# ELRS.net
KiCad netlist of a schematic drawn in Altium Designer
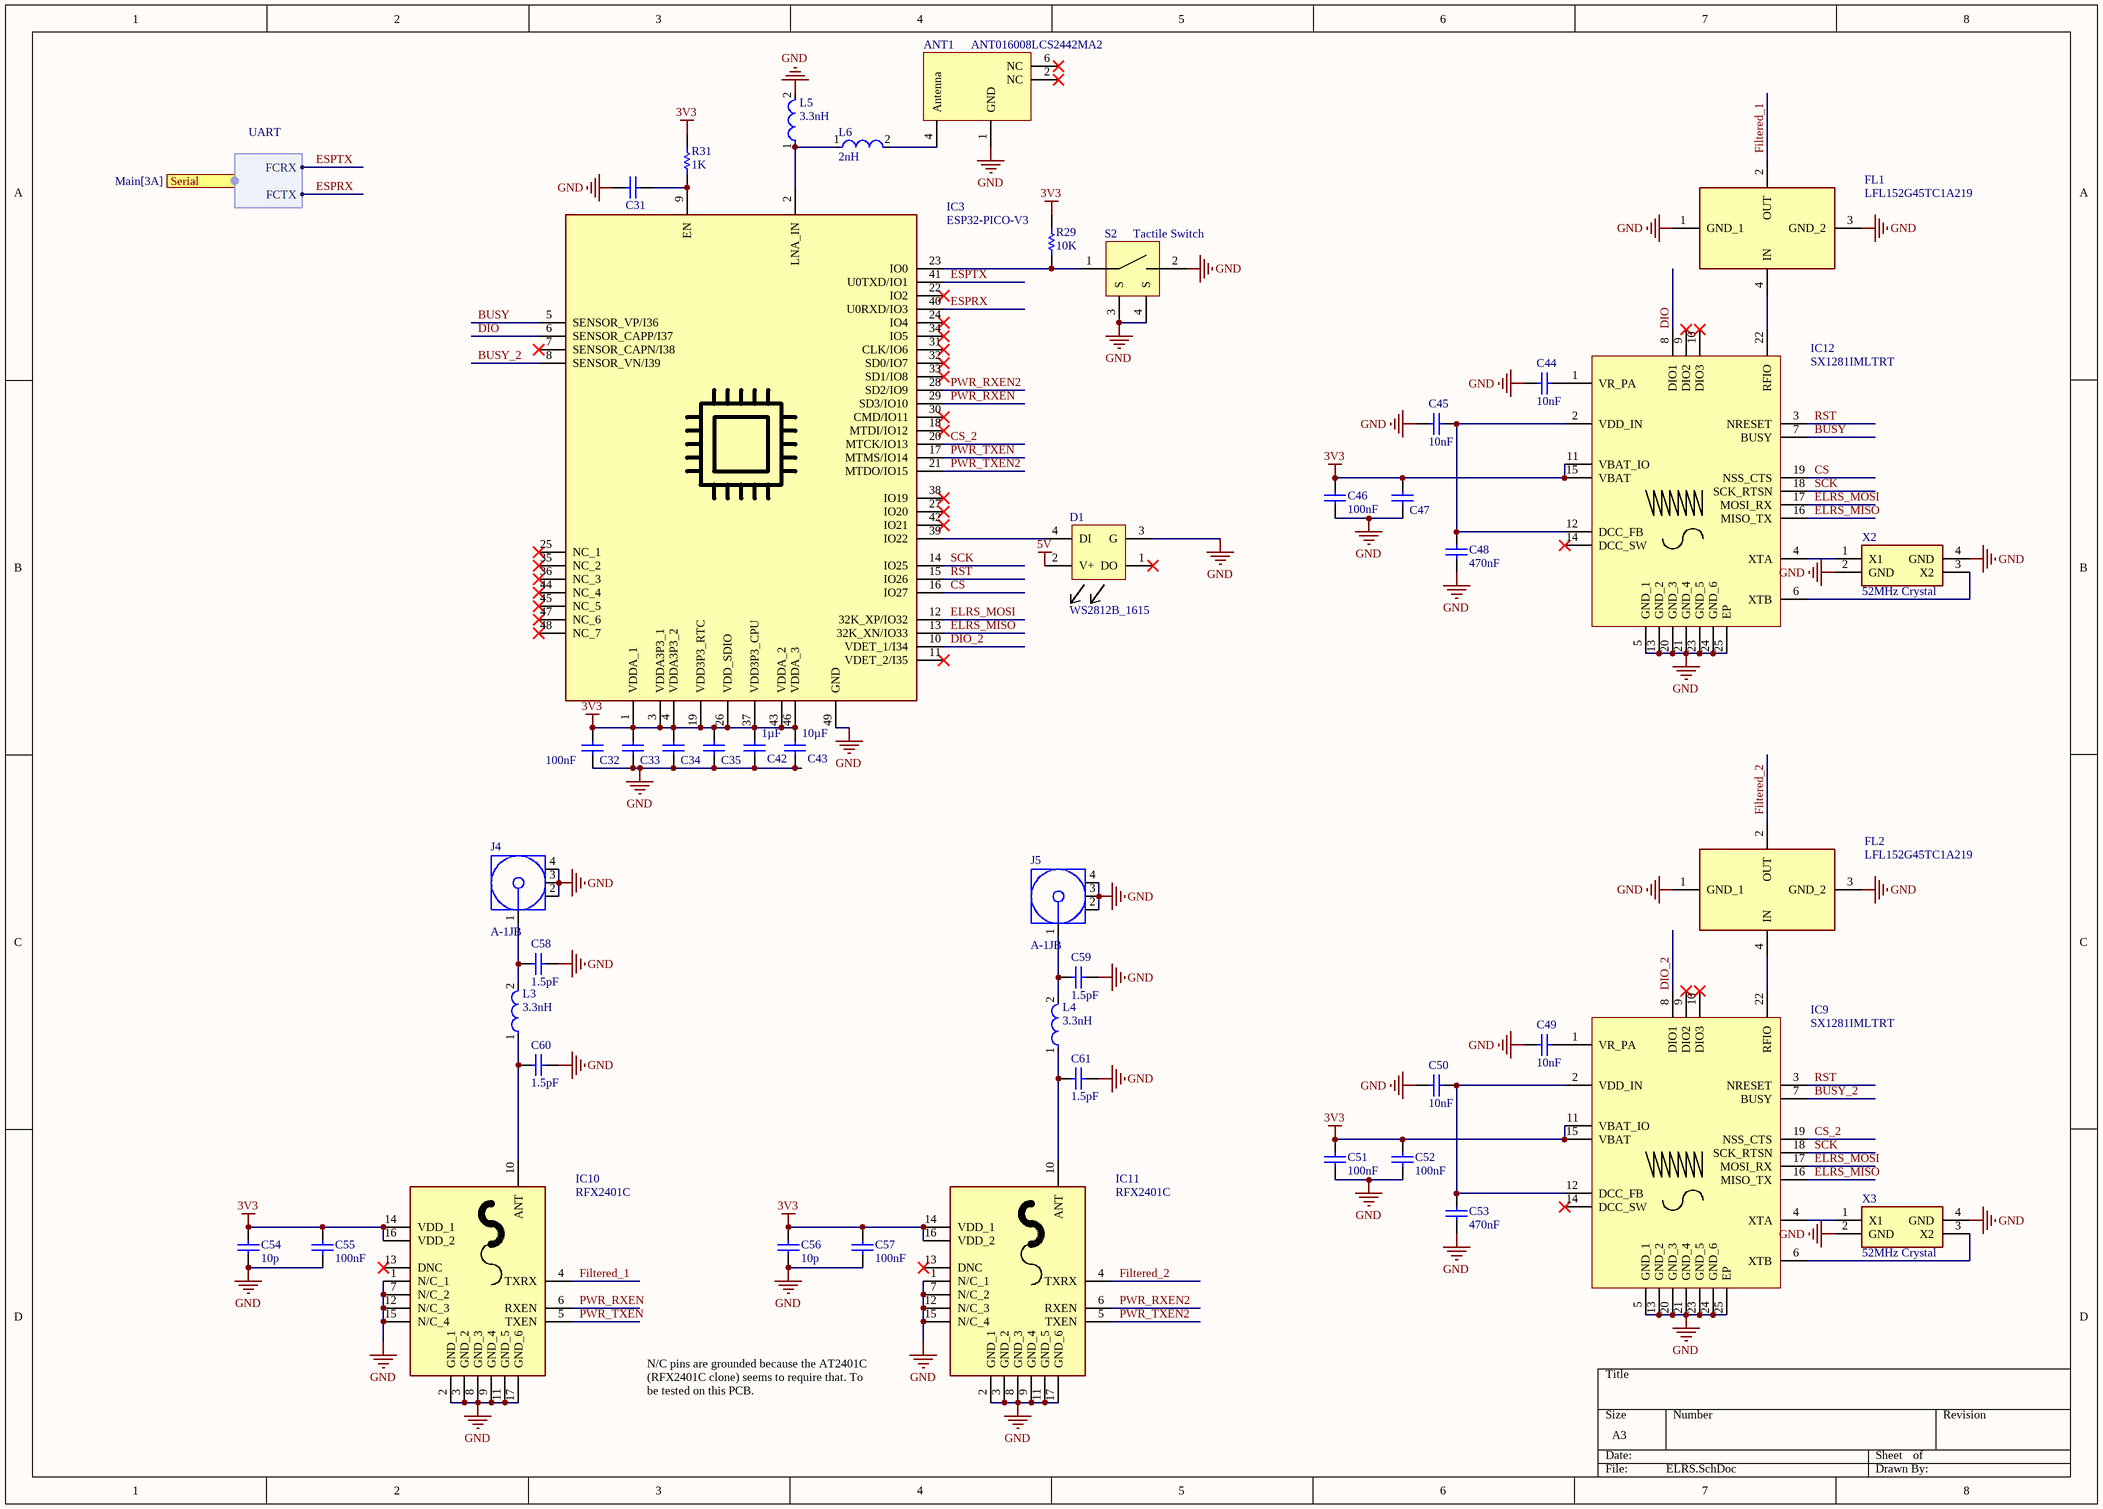
[diagram p0: ELRS.SchDoc]

(export (version "E")
  (design (tool "Eeschema 10.0.6"))
  (components
    (comp (ref "ANT1")
      (value "ANT016008LCS2442MA2")
      (footprint "Custom Components:ANT016008LCS2442MA2")
      (description "Antenna")
      (fields (field (name "MOUSER PART NUMBER") "810-ANT168LCS2442MA2"))
      (libsource (lib "Custom Components") (part "ANT016008LCS2442MA2"))
    )
    (comp (ref "C31")
      (value "100nF")
      (footprint "WCAP-CSGP_0603_L1.6W0.8H0.8_Reflow")
      (description "WCAP-CSGP Multilayer Ceramic Chip Capacitor, General Purpose, size 0603, X7R, 100nF, 50VDC")
      (fields
        (field (name "MANUFACTURER PART NUMBER") "885012206095")
        (field (name "MANUFACTURER") "Wurth Elektronik")
      )
      (libsource (lib "Altium_WCAP-CSGP (rev22f)") (part "885012206095"))
    )
    (comp (ref "C32")
      (value "100nF")
      (footprint "WCAP-CSGP_0603_L1.6W0.8H0.8_Reflow")
      (description "WCAP-CSGP Multilayer Ceramic Chip Capacitor, General Purpose, size 0603, X7R, 100nF, 50VDC")
      (fields
        (field (name "MANUFACTURER PART NUMBER") "885012206095")
        (field (name "MANUFACTURER") "Wurth Elektronik")
      )
      (libsource (lib "Altium_WCAP-CSGP (rev22f)") (part "885012206095"))
    )
    (comp (ref "C33")
      (value "100nF")
      (footprint "WCAP-CSGP_0603_L1.6W0.8H0.8_Reflow")
      (description "WCAP-CSGP Multilayer Ceramic Chip Capacitor, General Purpose, size 0603, X7R, 100nF, 50VDC")
      (fields
        (field (name "MANUFACTURER PART NUMBER") "885012206095")
        (field (name "MANUFACTURER") "Wurth Elektronik")
      )
      (libsource (lib "Altium_WCAP-CSGP (rev22f)") (part "885012206095"))
    )
    (comp (ref "C34")
      (value "100nF")
      (footprint "WCAP-CSGP_0603_L1.6W0.8H0.8_Reflow")
      (description "WCAP-CSGP Multilayer Ceramic Chip Capacitor, General Purpose, size 0603, X7R, 100nF, 50VDC")
      (fields
        (field (name "MANUFACTURER PART NUMBER") "885012206095")
        (field (name "MANUFACTURER") "Wurth Elektronik")
      )
      (libsource (lib "Altium_WCAP-CSGP (rev22f)") (part "885012206095"))
    )
    (comp (ref "C35")
      (value "100nF")
      (footprint "WCAP-CSGP_0603_L1.6W0.8H0.8_Reflow")
      (description "WCAP-CSGP Multilayer Ceramic Chip Capacitor, General Purpose, size 0603, X7R, 100nF, 50VDC")
      (fields
        (field (name "MANUFACTURER PART NUMBER") "885012206095")
        (field (name "MANUFACTURER") "Wurth Elektronik")
      )
      (libsource (lib "Altium_WCAP-CSGP (rev22f)") (part "885012206095"))
    )
    (comp (ref "C42")
      (value "1µF")
      (footprint "WCAP-CSGP_0603_L1.6W0.8H0.8_Reflow")
      (description "WCAP-CSGP Multilayer Ceramic Chip Capacitor, General Purpose, size 0603, X7R, 1µF, 25VDC")
      (fields
        (field (name "MANUFACTURER PART NUMBER") "885012206076")
        (field (name "MANUFACTURER") "Wurth Elektronik")
      )
      (libsource (lib "Altium_WCAP-CSGP (rev22f)") (part "885012206076"))
    )
    (comp (ref "C43")
      (value "10µF")
      (footprint "WCAP-CSGP_0603_L1.6W0.8H0.8_Reflow")
      (description "WCAP-CSGP Multilayer Ceramic Chip Capacitor, General Purpose, size 0603, X5R, 10µF, 25VDC")
      (fields
        (field (name "MANUFACTURER PART NUMBER") "885012106031")
        (field (name "MANUFACTURER") "Wurth Elektronik")
      )
      (libsource (lib "Altium_WCAP-CSGP (rev22f)") (part "885012106031"))
    )
    (comp (ref "C44")
      (value "10nF")
      (footprint "0402 cap")
      (libsource (lib "Custom Components") (part "Capacitor 0402 100nF"))
    )
    (comp (ref "C45")
      (value "10nF")
      (footprint "0402 cap")
      (libsource (lib "Custom Components") (part "Capacitor 0402 100nF"))
    )
    (comp (ref "C46")
      (value "100nF")
      (footprint "0402 cap")
      (libsource (lib "Custom Components") (part "Capacitor 0402 100nF"))
    )
    (comp (ref "C47")
      (value "100nF")
      (footprint "WCAP-CSGP_0603_L1.6W0.8H0.8_Reflow")
      (description "WCAP-CSGP Multilayer Ceramic Chip Capacitor, General Purpose, size 0603, X7R, 100nF, 50VDC")
      (fields
        (field (name "MANUFACTURER PART NUMBER") "885012206095")
        (field (name "MANUFACTURER") "Wurth Elektronik")
      )
      (libsource (lib "Altium_WCAP-CSGP (rev22f)") (part "885012206095"))
    )
    (comp (ref "C48")
      (value "470nF")
      (footprint "0402 cap")
      (libsource (lib "Custom Components") (part "Capacitor 0402 100nF"))
    )
    (comp (ref "C49")
      (value "10nF")
      (footprint "0402 cap")
      (libsource (lib "Custom Components") (part "Capacitor 0402 100nF"))
    )
    (comp (ref "C50")
      (value "10nF")
      (footprint "0402 cap")
      (libsource (lib "Custom Components") (part "Capacitor 0402 100nF"))
    )
    (comp (ref "C51")
      (value "100nF")
      (footprint "0402 cap")
      (libsource (lib "Custom Components") (part "Capacitor 0402 100nF"))
    )
    (comp (ref "C52")
      (value "100nF")
      (footprint "0402 cap")
      (libsource (lib "Custom Components") (part "Capacitor 0402 100nF"))
    )
    (comp (ref "C53")
      (value "470nF")
      (footprint "0402 cap")
      (libsource (lib "Custom Components") (part "Capacitor 0402 100nF"))
    )
    (comp (ref "C54")
      (value "10p")
      (footprint "0402 cap")
      (libsource (lib "Custom Components") (part "Capacitor 0402 100nF"))
    )
    (comp (ref "C55")
      (value "100nF")
      (footprint "0402 cap")
      (libsource (lib "Custom Components") (part "Capacitor 0402 100nF"))
    )
    (comp (ref "C56")
      (value "10p")
      (footprint "0402 cap")
      (libsource (lib "Custom Components") (part "Capacitor 0402 100nF"))
    )
    (comp (ref "C57")
      (value "100nF")
      (footprint "0402 cap")
      (libsource (lib "Custom Components") (part "Capacitor 0402 100nF"))
    )
    (comp (ref "C58")
      (value "1.5pF")
      (footprint "0402 cap")
      (description "CL05C1R5BB5NNNC")
      (libsource (lib "Custom Components") (part "Capacitor 0402 100nF"))
    )
    (comp (ref "C59")
      (value "1.5pF")
      (footprint "0402 cap")
      (description "CL05C1R5BB5NNNC")
      (libsource (lib "Custom Components") (part "Capacitor 0402 100nF"))
    )
    (comp (ref "C60")
      (value "1.5pF")
      (footprint "0402 cap")
      (description "CL05C1R5BB5NNNC")
      (libsource (lib "Custom Components") (part "Capacitor 0402 100nF"))
    )
    (comp (ref "C61")
      (value "1.5pF")
      (footprint "0402 cap")
      (description "CL05C1R5BB5NNNC")
      (libsource (lib "Custom Components") (part "Capacitor 0402 100nF"))
    )
    (comp (ref "D1")
      (value "WS2812B_1615")
      (footprint "WS2812B_1615")
      (description "XINGLIGHT XL-1615RGBC-WS2812B")
      (libsource (lib "Custom Components") (part "WS2812B_1615"))
    )
    (comp (ref "FL1")
      (value "LFL152G45TC1A219")
      (footprint "Custom Components:LFL152G45TC1A219")
      (description "Filter")
      (fields (field (name "MOUSER PART NUMBER") "81-LFL152G45TC1A219"))
      (libsource (lib "*") (part "LFL152G45TC1A219"))
    )
    (comp (ref "FL2")
      (value "LFL152G45TC1A219")
      (footprint "Custom Components:LFL152G45TC1A219")
      (description "Filter")
      (fields (field (name "MOUSER PART NUMBER") "81-LFL152G45TC1A219"))
      (libsource (lib "*") (part "LFL152G45TC1A219"))
    )
    (comp (ref "IC3")
      (value "ESP32-PICO-V3")
      (footprint "Custom Components:ESP32PICOV3")
      (description "Integrated Circuit")
      (fields (field (name "MOUSER PART NUMBER") "356-ESP32-PICO-V3"))
      (libsource (lib "Custom Components") (part "ESP32-PICO-V3"))
    )
    (comp (ref "IC9")
      (value "SX1281IMLTRT")
      (footprint "Custom Components:QFN50P400X400X100-25N-D")
      (description "Integrated Circuit")
      (fields (field (name "MOUSER PART NUMBER") "947-SX1281IMLTRT"))
      (libsource (lib "Custom Components") (part "SX1281IMLTRT"))
    )
    (comp (ref "IC10")
      (value "RFX2401C")
      (footprint "Custom Components:QFN50P300X300X60-17N-D")
      (description "Integrated Circuit")
      (fields (field (name "MOUSER PART NUMBER") "477-RFX2401C"))
      (libsource (lib "Custom Components") (part "RFX2401C"))
    )
    (comp (ref "IC11")
      (value "RFX2401C")
      (footprint "Custom Components:QFN50P300X300X60-17N-D")
      (description "Integrated Circuit")
      (fields (field (name "MOUSER PART NUMBER") "477-RFX2401C"))
      (libsource (lib "Custom Components") (part "RFX2401C"))
    )
    (comp (ref "IC12")
      (value "SX1281IMLTRT")
      (footprint "Custom Components:QFN50P400X400X100-25N-D")
      (description "Integrated Circuit")
      (fields (field (name "MOUSER PART NUMBER") "947-SX1281IMLTRT"))
      (libsource (lib "Custom Components") (part "SX1281IMLTRT"))
    )
    (comp (ref "J4")
      (value "A-1JB")
      (footprint "AMPH-A-1JB_V")
      (description "AMC PCB Jack, 0 to 60 GHz, 60 V, -40 to 90 degC, 4-Pin SMD, RoHS, Tape and Reel")
      (fields (field (name "TOLERANCE") "10%"))
      (libsource (lib "Altium Content Vault") (part "CN-S-3F-RF4"))
    )
    (comp (ref "J5")
      (value "A-1JB")
      (footprint "AMPH-A-1JB_V")
      (description "AMC PCB Jack, 0 to 60 GHz, 60 V, -40 to 90 degC, 4-Pin SMD, RoHS, Tape and Reel")
      (fields (field (name "TOLERANCE") "10%"))
      (libsource (lib "Altium Content Vault") (part "CN-S-3F-RF4"))
    )
    (comp (ref "L3")
      (value "3.3nH")
      (footprint "FP-LQW15AN_00-W0_6-0_1-MFG")
      (description "MLG1005S3N3BT000")
      (libsource (lib "Altium Content Vault") (part "725321dda6339637d4d059423bc1c3c"))
    )
    (comp (ref "L4")
      (value "3.3nH")
      (footprint "FP-LQW15AN_00-W0_6-0_1-MFG")
      (description "MLG1005S3N3BT000")
      (libsource (lib "Altium Content Vault") (part "725321dda6339637d4d059423bc1c3c"))
    )
    (comp (ref "L5")
      (value "3.3nH")
      (footprint "FP-LQW15AN_00-W0_6-0_1-MFG")
      (description "MLG1005S3N3BT000")
      (libsource (lib "Altium Content Vault") (part "725321dda6339637d4d059423bc1c3c"))
    )
    (comp (ref "L6")
      (value "2nH")
      (footprint "FP-LQW15AN_00-W0_6-0_1-MFG")
      (description "MLG1005S3N3BT000")
      (libsource (lib "Altium Content Vault") (part "725321dda6339637d4d059423bc1c3c"))
    )
    (comp (ref "R29")
      (value "10K")
      (footprint "Custom Components:0402 resistor")
      (libsource (lib "Custom Components") (part "Resistor 0402 1K"))
    )
    (comp (ref "R31")
      (value "1K")
      (footprint "Custom Components:0402 resistor")
      (libsource (lib "Custom Components") (part "Resistor 0402 1K"))
    )
    (comp (ref "S2")
      (value "Tactile Switch")
      (footprint "Tactile Switch")
      (libsource (lib "Custom Components") (part "Tactile Switch"))
    )
    (comp (ref "X2")
      (value "52MHz Crystal")
      (footprint "2016 Crystal")
      (description "HCI XC21M4-52.000-F10NNHPL")
      (libsource (lib "Custom Components") (part "HCI XC21M4-52.000"))
    )
    (comp (ref "X3")
      (value "52MHz Crystal")
      (footprint "2016 Crystal")
      (description "HCI XC21M4-52.000-F10NNHPL")
      (libsource (lib "Custom Components") (part "HCI XC21M4-52.000"))
    )
  )
  (nets
    (net (code "2") (name "/BUSY") (class "Default")
      (node (ref "IC12") (pin "7") (pinfunction "BUSY_7") (pintype "passive"))
      (node (ref "IC3") (pin "5") (pinfunction "SENSOR_VP/I36_5") (pintype "passive"))
    )
    (net (code "3") (name "/BUSY_2") (class "Default")
      (node (ref "IC3") (pin "8") (pinfunction "SENSOR_VN/I39_8") (pintype "passive"))
      (node (ref "IC9") (pin "7") (pinfunction "BUSY_7") (pintype "passive"))
    )
    (net (code "4") (name "/CS") (class "Default")
      (node (ref "IC12") (pin "19") (pinfunction "NSS_CTS_19") (pintype "passive"))
      (node (ref "IC3") (pin "16") (pinfunction "IO27_16") (pintype "passive"))
    )
    (net (code "5") (name "/CS_2") (class "Default")
      (node (ref "IC3") (pin "20") (pinfunction "MTCK/IO13_20") (pintype "passive"))
      (node (ref "IC9") (pin "19") (pinfunction "NSS_CTS_19") (pintype "passive"))
    )
    (net (code "6") (name "/DIO") (class "Default")
      (node (ref "IC12") (pin "8") (pinfunction "DIO1_8") (pintype "passive"))
      (node (ref "IC3") (pin "6") (pinfunction "SENSOR_CAPP/I37_6") (pintype "passive"))
    )
    (net (code "7") (name "/DIO_2") (class "Default")
      (node (ref "IC3") (pin "10") (pinfunction "VDET_1/I34_10") (pintype "passive"))
      (node (ref "IC9") (pin "8") (pinfunction "DIO1_8") (pintype "passive"))
    )
    (net (code "8") (name "/ELRS_MISO") (class "Default")
      (node (ref "IC12") (pin "16") (pinfunction "MISO_TX_16") (pintype "passive"))
      (node (ref "IC3") (pin "13") (pinfunction "32K_XN/IO33_13") (pintype "passive"))
      (node (ref "IC9") (pin "16") (pinfunction "MISO_TX_16") (pintype "passive"))
    )
    (net (code "9") (name "/ELRS_MOSI") (class "Default")
      (node (ref "IC12") (pin "17") (pinfunction "MOSI_RX_17") (pintype "passive"))
      (node (ref "IC3") (pin "12") (pinfunction "32K_XP/IO32_12") (pintype "passive"))
      (node (ref "IC9") (pin "17") (pinfunction "MOSI_RX_17") (pintype "passive"))
    )
    (net (code "10") (name "/ESPRX") (class "Default")
      (node (ref "IC3") (pin "40") (pinfunction "U0RXD/IO3_40") (pintype "passive"))
    )
    (net (code "11") (name "/ESPTX") (class "Default")
      (node (ref "IC3") (pin "41") (pinfunction "U0TXD/IO1_41") (pintype "passive"))
    )
    (net (code "12") (name "/Filtered_1") (class "Default")
      (node (ref "FL1") (pin "2") (pinfunction "OUT_2") (pintype "passive"))
      (node (ref "IC10") (pin "4") (pinfunction "TXRX_4") (pintype "passive"))
    )
    (net (code "13") (name "/Filtered_2") (class "Default")
      (node (ref "FL2") (pin "2") (pinfunction "OUT_2") (pintype "passive"))
      (node (ref "IC11") (pin "4") (pinfunction "TXRX_4") (pintype "passive"))
    )
    (net (code "14") (name "/PWR_RXEN") (class "Default")
      (node (ref "IC10") (pin "6") (pinfunction "RXEN_6") (pintype "passive"))
      (node (ref "IC3") (pin "29") (pinfunction "SD3/IO10_29") (pintype "passive"))
    )
    (net (code "15") (name "/PWR_RXEN2") (class "Default")
      (node (ref "IC11") (pin "6") (pinfunction "RXEN_6") (pintype "passive"))
      (node (ref "IC3") (pin "28") (pinfunction "SD2/IO9_28") (pintype "passive"))
    )
    (net (code "16") (name "/PWR_TXEN") (class "Default")
      (node (ref "IC10") (pin "5") (pinfunction "TXEN_5") (pintype "passive"))
      (node (ref "IC3") (pin "17") (pinfunction "MTMS/IO14_17") (pintype "passive"))
    )
    (net (code "17") (name "/PWR_TXEN2") (class "Default")
      (node (ref "IC11") (pin "5") (pinfunction "TXEN_5") (pintype "passive"))
      (node (ref "IC3") (pin "21") (pinfunction "MTDO/IO15_21") (pintype "passive"))
    )
    (net (code "18") (name "/RST") (class "Default")
      (node (ref "IC12") (pin "3") (pinfunction "NRESET_3") (pintype "passive"))
      (node (ref "IC3") (pin "15") (pinfunction "IO26_15") (pintype "passive"))
      (node (ref "IC9") (pin "3") (pinfunction "NRESET_3") (pintype "passive"))
    )
    (net (code "19") (name "/SCK") (class "Default")
      (node (ref "IC12") (pin "18") (pinfunction "SCK_RTSN_18") (pintype "passive"))
      (node (ref "IC3") (pin "14") (pinfunction "IO25_14") (pintype "passive"))
      (node (ref "IC9") (pin "18") (pinfunction "SCK_RTSN_18") (pintype "passive"))
    )
    (net (code "21") (name "3V3") (class "Default")
      (node (ref "C32") (pin "2") (pinfunction "2_2") (pintype "passive"))
      (node (ref "C33") (pin "2") (pinfunction "2_2") (pintype "passive"))
      (node (ref "C34") (pin "2") (pinfunction "2_2") (pintype "passive"))
      (node (ref "C35") (pin "2") (pinfunction "2_2") (pintype "passive"))
      (node (ref "C42") (pin "2") (pinfunction "2_2") (pintype "passive"))
      (node (ref "C43") (pin "2") (pinfunction "2_2") (pintype "passive"))
      (node (ref "C46") (pin "2") (pinfunction "2_2") (pintype "passive"))
      (node (ref "C47") (pin "2") (pinfunction "2_2") (pintype "passive"))
      (node (ref "C51") (pin "2") (pinfunction "2_2") (pintype "passive"))
      (node (ref "C52") (pin "2") (pinfunction "2_2") (pintype "passive"))
      (node (ref "C54") (pin "2") (pinfunction "2_2") (pintype "passive"))
      (node (ref "C55") (pin "2") (pinfunction "2_2") (pintype "passive"))
      (node (ref "C56") (pin "2") (pinfunction "2_2") (pintype "passive"))
      (node (ref "C57") (pin "2") (pinfunction "2_2") (pintype "passive"))
      (node (ref "IC10") (pin "14") (pinfunction "VDD_1_14") (pintype "passive"))
      (node (ref "IC10") (pin "16") (pinfunction "VDD_2_16") (pintype "passive"))
      (node (ref "IC11") (pin "14") (pinfunction "VDD_1_14") (pintype "passive"))
      (node (ref "IC11") (pin "16") (pinfunction "VDD_2_16") (pintype "passive"))
      (node (ref "IC12") (pin "11") (pinfunction "VBAT_IO_11") (pintype "passive"))
      (node (ref "IC12") (pin "15") (pinfunction "VBAT_15") (pintype "passive"))
      (node (ref "IC3") (pin "1") (pinfunction "VDDA_1_1") (pintype "passive"))
      (node (ref "IC3") (pin "19") (pinfunction "VDD3P3_RTC_19") (pintype "passive"))
      (node (ref "IC3") (pin "26") (pinfunction "VDD_SDIO_26") (pintype "passive"))
      (node (ref "IC3") (pin "3") (pinfunction "VDDA3P3_1_3") (pintype "passive"))
      (node (ref "IC3") (pin "37") (pinfunction "VDD3P3_CPU_37") (pintype "passive"))
      (node (ref "IC3") (pin "4") (pinfunction "VDDA3P3_2_4") (pintype "passive"))
      (node (ref "IC3") (pin "43") (pinfunction "VDDA_2_43") (pintype "passive"))
      (node (ref "IC3") (pin "46") (pinfunction "VDDA_3_46") (pintype "passive"))
      (node (ref "IC9") (pin "11") (pinfunction "VBAT_IO_11") (pintype "passive"))
      (node (ref "IC9") (pin "15") (pinfunction "VBAT_15") (pintype "passive"))
      (node (ref "R29") (pin "2") (pinfunction "2_2") (pintype "passive"))
      (node (ref "R31") (pin "2") (pinfunction "2_2") (pintype "passive"))
    )
    (net (code "22") (name "5V") (class "Default")
      (node (ref "D1") (pin "2") (pinfunction "V+_2") (pintype "passive"))
    )
    (net (code "23") (name "GND") (class "Default")
      (node (ref "ANT1") (pin "1") (pinfunction "GND_1") (pintype "passive"))
      (node (ref "C31") (pin "2") (pinfunction "2_2") (pintype "passive"))
      (node (ref "C32") (pin "1") (pinfunction "1_1") (pintype "passive"))
      (node (ref "C33") (pin "1") (pinfunction "1_1") (pintype "passive"))
      (node (ref "C34") (pin "1") (pinfunction "1_1") (pintype "passive"))
      (node (ref "C35") (pin "1") (pinfunction "1_1") (pintype "passive"))
      (node (ref "C42") (pin "1") (pinfunction "1_1") (pintype "passive"))
      (node (ref "C43") (pin "1") (pinfunction "1_1") (pintype "passive"))
      (node (ref "C44") (pin "1") (pinfunction "1_1") (pintype "passive"))
      (node (ref "C45") (pin "1") (pinfunction "1_1") (pintype "passive"))
      (node (ref "C46") (pin "1") (pinfunction "1_1") (pintype "passive"))
      (node (ref "C47") (pin "1") (pinfunction "1_1") (pintype "passive"))
      (node (ref "C48") (pin "1") (pinfunction "1_1") (pintype "passive"))
      (node (ref "C49") (pin "1") (pinfunction "1_1") (pintype "passive"))
      (node (ref "C50") (pin "1") (pinfunction "1_1") (pintype "passive"))
      (node (ref "C51") (pin "1") (pinfunction "1_1") (pintype "passive"))
      (node (ref "C52") (pin "1") (pinfunction "1_1") (pintype "passive"))
      (node (ref "C53") (pin "1") (pinfunction "1_1") (pintype "passive"))
      (node (ref "C54") (pin "1") (pinfunction "1_1") (pintype "passive"))
      (node (ref "C55") (pin "1") (pinfunction "1_1") (pintype "passive"))
      (node (ref "C56") (pin "1") (pinfunction "1_1") (pintype "passive"))
      (node (ref "C57") (pin "1") (pinfunction "1_1") (pintype "passive"))
      (node (ref "C58") (pin "2") (pinfunction "2_2") (pintype "passive"))
      (node (ref "C59") (pin "2") (pinfunction "2_2") (pintype "passive"))
      (node (ref "C60") (pin "2") (pinfunction "2_2") (pintype "passive"))
      (node (ref "C61") (pin "2") (pinfunction "2_2") (pintype "passive"))
      (node (ref "D1") (pin "3") (pinfunction "G_3") (pintype "passive"))
      (node (ref "FL1") (pin "1") (pinfunction "GND_1_1") (pintype "passive"))
      (node (ref "FL1") (pin "3") (pinfunction "GND_2_3") (pintype "passive"))
      (node (ref "FL2") (pin "1") (pinfunction "GND_1_1") (pintype "passive"))
      (node (ref "FL2") (pin "3") (pinfunction "GND_2_3") (pintype "passive"))
      (node (ref "IC10") (pin "1") (pinfunction "N/C_1_1") (pintype "passive"))
      (node (ref "IC10") (pin "11") (pinfunction "GND_5_11") (pintype "passive"))
      (node (ref "IC10") (pin "12") (pinfunction "N/C_3_12") (pintype "passive"))
      (node (ref "IC10") (pin "15") (pinfunction "N/C_4_15") (pintype "passive"))
      (node (ref "IC10") (pin "17") (pinfunction "GND_6_17") (pintype "passive"))
      (node (ref "IC10") (pin "2") (pinfunction "GND_1_2") (pintype "passive"))
      (node (ref "IC10") (pin "3") (pinfunction "GND_2_3") (pintype "passive"))
      (node (ref "IC10") (pin "7") (pinfunction "N/C_2_7") (pintype "passive"))
      (node (ref "IC10") (pin "8") (pinfunction "GND_3_8") (pintype "passive"))
      (node (ref "IC10") (pin "9") (pinfunction "GND_4_9") (pintype "passive"))
      (node (ref "IC11") (pin "1") (pinfunction "N/C_1_1") (pintype "passive"))
      (node (ref "IC11") (pin "11") (pinfunction "GND_5_11") (pintype "passive"))
      (node (ref "IC11") (pin "12") (pinfunction "N/C_3_12") (pintype "passive"))
      (node (ref "IC11") (pin "15") (pinfunction "N/C_4_15") (pintype "passive"))
      (node (ref "IC11") (pin "17") (pinfunction "GND_6_17") (pintype "passive"))
      (node (ref "IC11") (pin "2") (pinfunction "GND_1_2") (pintype "passive"))
      (node (ref "IC11") (pin "3") (pinfunction "GND_2_3") (pintype "passive"))
      (node (ref "IC11") (pin "7") (pinfunction "N/C_2_7") (pintype "passive"))
      (node (ref "IC11") (pin "8") (pinfunction "GND_3_8") (pintype "passive"))
      (node (ref "IC11") (pin "9") (pinfunction "GND_4_9") (pintype "passive"))
      (node (ref "IC12") (pin "13") (pinfunction "GND_2_13") (pintype "passive"))
      (node (ref "IC12") (pin "20") (pinfunction "GND_3_20") (pintype "passive"))
      (node (ref "IC12") (pin "21") (pinfunction "GND_4_21") (pintype "passive"))
      (node (ref "IC12") (pin "23") (pinfunction "GND_5_23") (pintype "passive"))
      (node (ref "IC12") (pin "24") (pinfunction "GND_6_24") (pintype "passive"))
      (node (ref "IC12") (pin "25") (pinfunction "EP_25") (pintype "passive"))
      (node (ref "IC12") (pin "5") (pinfunction "GND_1_5") (pintype "passive"))
      (node (ref "IC3") (pin "49") (pinfunction "GND_49") (pintype "passive"))
      (node (ref "IC9") (pin "13") (pinfunction "GND_2_13") (pintype "passive"))
      (node (ref "IC9") (pin "20") (pinfunction "GND_3_20") (pintype "passive"))
      (node (ref "IC9") (pin "21") (pinfunction "GND_4_21") (pintype "passive"))
      (node (ref "IC9") (pin "23") (pinfunction "GND_5_23") (pintype "passive"))
      (node (ref "IC9") (pin "24") (pinfunction "GND_6_24") (pintype "passive"))
      (node (ref "IC9") (pin "25") (pinfunction "EP_25") (pintype "passive"))
      (node (ref "IC9") (pin "5") (pinfunction "GND_1_5") (pintype "passive"))
      (node (ref "J4") (pin "2") (pinfunction "2_2") (pintype "passive"))
      (node (ref "J4") (pin "3") (pinfunction "3_3") (pintype "passive"))
      (node (ref "J4") (pin "4") (pinfunction "4_4") (pintype "passive"))
      (node (ref "J5") (pin "2") (pinfunction "2_2") (pintype "passive"))
      (node (ref "J5") (pin "3") (pinfunction "3_3") (pintype "passive"))
      (node (ref "J5") (pin "4") (pinfunction "4_4") (pintype "passive"))
      (node (ref "L5") (pin "2") (pinfunction "2_2") (pintype "passive"))
      (node (ref "S2") (pin "2") (pintype "passive"))
      (node (ref "S2") (pin "3") (pinfunction "S_3") (pintype "passive"))
      (node (ref "S2") (pin "4") (pinfunction "S_4") (pintype "passive"))
      (node (ref "X2") (pin "2") (pinfunction "GND_2") (pintype "passive"))
      (node (ref "X2") (pin "4") (pinfunction "GND_4") (pintype "passive"))
      (node (ref "X3") (pin "2") (pinfunction "GND_2") (pintype "passive"))
      (node (ref "X3") (pin "4") (pinfunction "GND_4") (pintype "passive"))
    )
    (net (code "24") (name "Net-(ANT1-Antenna)") (class "Default")
      (node (ref "ANT1") (pin "4") (pinfunction "Antenna_4") (pintype "passive"))
      (node (ref "L6") (pin "2") (pinfunction "2_2") (pintype "passive"))
    )
    (net (code "25") (name "Net-(C58-Pad1)") (class "Default")
      (node (ref "C58") (pin "1") (pinfunction "1_1") (pintype "passive"))
      (node (ref "J4") (pin "1") (pinfunction "1_1") (pintype "passive"))
      (node (ref "L3") (pin "2") (pinfunction "2_2") (pintype "passive"))
    )
    (net (code "26") (name "Net-(C59-Pad1)") (class "Default")
      (node (ref "C59") (pin "1") (pinfunction "1_1") (pintype "passive"))
      (node (ref "J5") (pin "1") (pinfunction "1_1") (pintype "passive"))
      (node (ref "L4") (pin "2") (pinfunction "2_2") (pintype "passive"))
    )
    (net (code "27") (name "Net-(D1-DI)") (class "Default")
      (node (ref "D1") (pin "4") (pinfunction "DI_4") (pintype "passive"))
      (node (ref "IC3") (pin "39") (pinfunction "IO22_39") (pintype "passive"))
    )
    (net (code "28") (name "Net-(FL1-IN)") (class "Default")
      (node (ref "FL1") (pin "4") (pinfunction "IN_4") (pintype "passive"))
      (node (ref "IC12") (pin "22") (pinfunction "RFIO_22") (pintype "passive"))
    )
    (net (code "29") (name "Net-(FL2-IN)") (class "Default")
      (node (ref "FL2") (pin "4") (pinfunction "IN_4") (pintype "passive"))
      (node (ref "IC9") (pin "22") (pinfunction "RFIO_22") (pintype "passive"))
    )
    (net (code "30") (name "Net-(IC3-EN)") (class "Default")
      (node (ref "C31") (pin "1") (pinfunction "1_1") (pintype "passive"))
      (node (ref "IC3") (pin "9") (pinfunction "EN_9") (pintype "passive"))
      (node (ref "R31") (pin "1") (pinfunction "1_1") (pintype "passive"))
    )
    (net (code "31") (name "Net-(IC3-IO0)") (class "Default")
      (node (ref "IC3") (pin "23") (pinfunction "IO0_23") (pintype "passive"))
      (node (ref "R29") (pin "1") (pinfunction "1_1") (pintype "passive"))
      (node (ref "S2") (pin "1") (pintype "passive"))
    )
    (net (code "32") (name "Net-(IC3-LNA_IN)") (class "Default")
      (node (ref "IC3") (pin "2") (pinfunction "LNA_IN_2") (pintype "passive"))
      (node (ref "L5") (pin "1") (pinfunction "1_1") (pintype "passive"))
      (node (ref "L6") (pin "1") (pinfunction "1_1") (pintype "passive"))
    )
    (net (code "33") (name "Net-(IC9-DCC_FB)") (class "Default")
      (node (ref "C50") (pin "2") (pinfunction "2_2") (pintype "passive"))
      (node (ref "C53") (pin "2") (pinfunction "2_2") (pintype "passive"))
      (node (ref "IC9") (pin "12") (pinfunction "DCC_FB_12") (pintype "passive"))
      (node (ref "IC9") (pin "2") (pinfunction "VDD_IN_2") (pintype "passive"))
    )
    (net (code "34") (name "Net-(IC9-VR_PA)") (class "Default")
      (node (ref "C49") (pin "2") (pinfunction "2_2") (pintype "passive"))
      (node (ref "IC9") (pin "1") (pinfunction "VR_PA_1") (pintype "passive"))
    )
    (net (code "35") (name "Net-(IC9-XTA)") (class "Default")
      (node (ref "IC9") (pin "4") (pinfunction "XTA_4") (pintype "passive"))
      (node (ref "X3") (pin "1") (pinfunction "X1_1") (pintype "passive"))
    )
    (net (code "36") (name "Net-(IC9-XTB)") (class "Default")
      (node (ref "IC9") (pin "6") (pinfunction "XTB_6") (pintype "passive"))
      (node (ref "X3") (pin "3") (pinfunction "X2_3") (pintype "passive"))
    )
    (net (code "37") (name "Net-(IC10-ANT)") (class "Default")
      (node (ref "C60") (pin "1") (pinfunction "1_1") (pintype "passive"))
      (node (ref "IC10") (pin "10") (pinfunction "ANT_10") (pintype "passive"))
      (node (ref "L3") (pin "1") (pinfunction "1_1") (pintype "passive"))
    )
    (net (code "38") (name "Net-(IC11-ANT)") (class "Default")
      (node (ref "C61") (pin "1") (pinfunction "1_1") (pintype "passive"))
      (node (ref "IC11") (pin "10") (pinfunction "ANT_10") (pintype "passive"))
      (node (ref "L4") (pin "1") (pinfunction "1_1") (pintype "passive"))
    )
    (net (code "39") (name "Net-(IC12-DCC_FB)") (class "Default")
      (node (ref "C45") (pin "2") (pinfunction "2_2") (pintype "passive"))
      (node (ref "C48") (pin "2") (pinfunction "2_2") (pintype "passive"))
      (node (ref "IC12") (pin "12") (pinfunction "DCC_FB_12") (pintype "passive"))
      (node (ref "IC12") (pin "2") (pinfunction "VDD_IN_2") (pintype "passive"))
    )
    (net (code "40") (name "Net-(IC12-VR_PA)") (class "Default")
      (node (ref "C44") (pin "2") (pinfunction "2_2") (pintype "passive"))
      (node (ref "IC12") (pin "1") (pinfunction "VR_PA_1") (pintype "passive"))
    )
    (net (code "41") (name "Net-(IC12-XTA)") (class "Default")
      (node (ref "IC12") (pin "4") (pinfunction "XTA_4") (pintype "passive"))
      (node (ref "X2") (pin "1") (pinfunction "X1_1") (pintype "passive"))
    )
    (net (code "42") (name "Net-(IC12-XTB)") (class "Default")
      (node (ref "IC12") (pin "6") (pinfunction "XTB_6") (pintype "passive"))
      (node (ref "X2") (pin "3") (pinfunction "X2_3") (pintype "passive"))
    )
    (net (code "43") (name "unconnected-(ANT1-NC-Pad2)") (class "Default")
      (node (ref "ANT1") (pin "2") (pinfunction "NC_2") (pintype "passive+no_connect"))
    )
    (net (code "44") (name "unconnected-(ANT1-NC-Pad6)") (class "Default")
      (node (ref "ANT1") (pin "6") (pinfunction "NC_6") (pintype "passive+no_connect"))
    )
    (net (code "45") (name "unconnected-(D1-DO-Pad1)") (class "Default")
      (node (ref "D1") (pin "1") (pinfunction "DO_1") (pintype "passive+no_connect"))
    )
    (net (code "46") (name "unconnected-(IC3-CLK{slash}IO6-Pad31)") (class "Default")
      (node (ref "IC3") (pin "31") (pinfunction "CLK/IO6_31") (pintype "passive+no_connect"))
    )
    (net (code "47") (name "unconnected-(IC3-CMD{slash}IO11-Pad30)") (class "Default")
      (node (ref "IC3") (pin "30") (pinfunction "CMD/IO11_30") (pintype "passive+no_connect"))
    )
    (net (code "48") (name "unconnected-(IC3-IO2-Pad22)") (class "Default")
      (node (ref "IC3") (pin "22") (pinfunction "IO2_22") (pintype "passive+no_connect"))
    )
    (net (code "49") (name "unconnected-(IC3-IO4-Pad24)") (class "Default")
      (node (ref "IC3") (pin "24") (pinfunction "IO4_24") (pintype "passive+no_connect"))
    )
    (net (code "50") (name "unconnected-(IC3-IO5-Pad34)") (class "Default")
      (node (ref "IC3") (pin "34") (pinfunction "IO5_34") (pintype "passive+no_connect"))
    )
    (net (code "51") (name "unconnected-(IC3-IO19-Pad38)") (class "Default")
      (node (ref "IC3") (pin "38") (pinfunction "IO19_38") (pintype "passive+no_connect"))
    )
    (net (code "52") (name "unconnected-(IC3-IO20-Pad27)") (class "Default")
      (node (ref "IC3") (pin "27") (pinfunction "IO20_27") (pintype "passive+no_connect"))
    )
    (net (code "53") (name "unconnected-(IC3-IO21-Pad42)") (class "Default")
      (node (ref "IC3") (pin "42") (pinfunction "IO21_42") (pintype "passive+no_connect"))
    )
    (net (code "54") (name "unconnected-(IC3-MTDI{slash}IO12-Pad18)") (class "Default")
      (node (ref "IC3") (pin "18") (pinfunction "MTDI/IO12_18") (pintype "passive+no_connect"))
    )
    (net (code "55") (name "unconnected-(IC3-NC_1-Pad25)") (class "Default")
      (node (ref "IC3") (pin "25") (pinfunction "NC_1_25") (pintype "passive+no_connect"))
    )
    (net (code "56") (name "unconnected-(IC3-NC_2-Pad35)") (class "Default")
      (node (ref "IC3") (pin "35") (pinfunction "NC_2_35") (pintype "passive+no_connect"))
    )
    (net (code "57") (name "unconnected-(IC3-NC_3-Pad36)") (class "Default")
      (node (ref "IC3") (pin "36") (pinfunction "NC_3_36") (pintype "passive+no_connect"))
    )
    (net (code "58") (name "unconnected-(IC3-NC_4-Pad44)") (class "Default")
      (node (ref "IC3") (pin "44") (pinfunction "NC_4_44") (pintype "passive+no_connect"))
    )
    (net (code "59") (name "unconnected-(IC3-NC_5-Pad45)") (class "Default")
      (node (ref "IC3") (pin "45") (pinfunction "NC_5_45") (pintype "passive+no_connect"))
    )
    (net (code "60") (name "unconnected-(IC3-NC_6-Pad47)") (class "Default")
      (node (ref "IC3") (pin "47") (pinfunction "NC_6_47") (pintype "passive+no_connect"))
    )
    (net (code "61") (name "unconnected-(IC3-NC_7-Pad48)") (class "Default")
      (node (ref "IC3") (pin "48") (pinfunction "NC_7_48") (pintype "passive+no_connect"))
    )
    (net (code "62") (name "unconnected-(IC3-SD0{slash}IO7-Pad32)") (class "Default")
      (node (ref "IC3") (pin "32") (pinfunction "SD0/IO7_32") (pintype "passive+no_connect"))
    )
    (net (code "63") (name "unconnected-(IC3-SD1{slash}IO8-Pad33)") (class "Default")
      (node (ref "IC3") (pin "33") (pinfunction "SD1/IO8_33") (pintype "passive+no_connect"))
    )
    (net (code "64") (name "unconnected-(IC3-SENSOR_CAPN{slash}I38-Pad7)") (class "Default")
      (node (ref "IC3") (pin "7") (pinfunction "SENSOR_CAPN/I38_7") (pintype "passive+no_connect"))
    )
    (net (code "65") (name "unconnected-(IC3-VDET_2{slash}I35-Pad11)") (class "Default")
      (node (ref "IC3") (pin "11") (pinfunction "VDET_2/I35_11") (pintype "passive+no_connect"))
    )
    (net (code "66") (name "unconnected-(IC9-DCC_SW-Pad14)") (class "Default")
      (node (ref "IC9") (pin "14") (pinfunction "DCC_SW_14") (pintype "passive+no_connect"))
    )
    (net (code "67") (name "unconnected-(IC9-DIO2-Pad9)") (class "Default")
      (node (ref "IC9") (pin "9") (pinfunction "DIO2_9") (pintype "passive+no_connect"))
    )
    (net (code "68") (name "unconnected-(IC9-DIO3-Pad10)") (class "Default")
      (node (ref "IC9") (pin "10") (pinfunction "DIO3_10") (pintype "passive+no_connect"))
    )
    (net (code "69") (name "unconnected-(IC10-DNC-Pad13)") (class "Default")
      (node (ref "IC10") (pin "13") (pinfunction "DNC_13") (pintype "passive+no_connect"))
    )
    (net (code "70") (name "unconnected-(IC11-DNC-Pad13)") (class "Default")
      (node (ref "IC11") (pin "13") (pinfunction "DNC_13") (pintype "passive+no_connect"))
    )
    (net (code "71") (name "unconnected-(IC12-DCC_SW-Pad14)") (class "Default")
      (node (ref "IC12") (pin "14") (pinfunction "DCC_SW_14") (pintype "passive+no_connect"))
    )
    (net (code "72") (name "unconnected-(IC12-DIO2-Pad9)") (class "Default")
      (node (ref "IC12") (pin "9") (pinfunction "DIO2_9") (pintype "passive+no_connect"))
    )
    (net (code "73") (name "unconnected-(IC12-DIO3-Pad10)") (class "Default")
      (node (ref "IC12") (pin "10") (pinfunction "DIO3_10") (pintype "passive+no_connect"))
    )
  )
)
